# SCP_Controller.net
KiCad netlist of a schematic drawn in Altium Designer
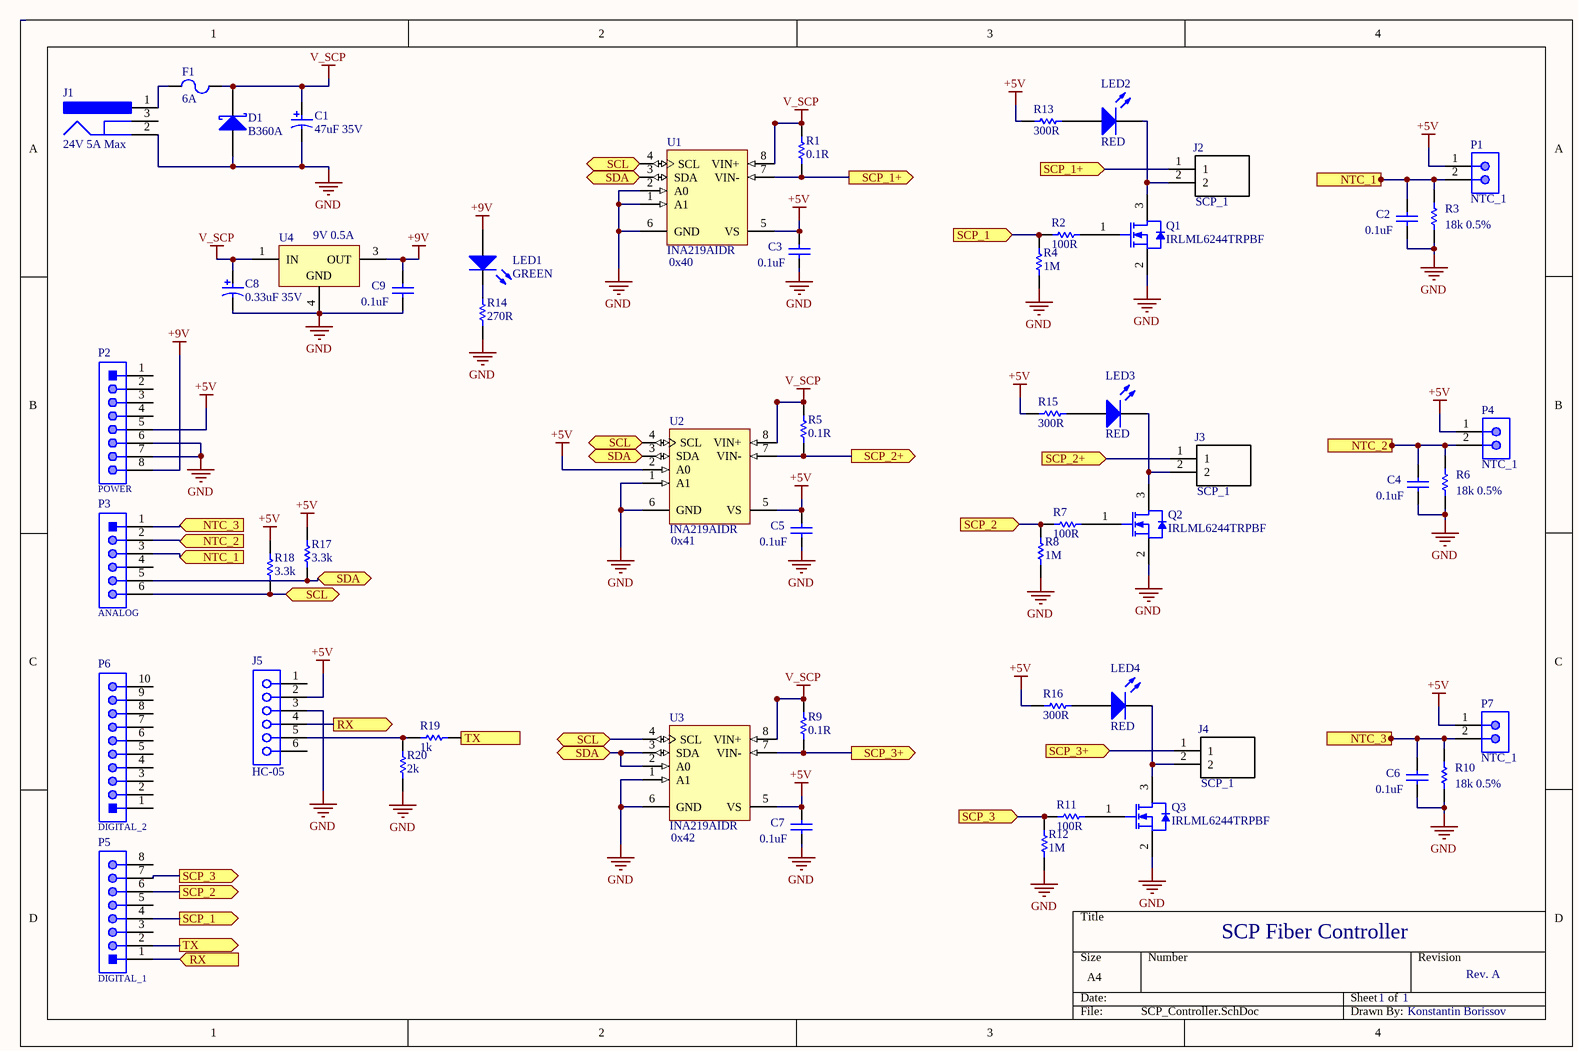
[diagram p0: SCP_Controller.SchDoc]

(export (version "E")
  (design (tool "Eeschema 10.0.6"))
  (components
    (comp (ref "C1")
      (value "47uF 35V")
      (footprint "PNSC-FP-V-D_V")
      (fields
        (field (name "MANUFACTURER") "Panasonic")
        (field (name "MANUFACTURER PART NUMBER") "EEE-1VA470WP")
        (field (name "TOLERANCE") "20%")
      )
      (libsource (lib "Altium Content Vault") (part "CAP-P-2"))
    )
    (comp (ref "C2")
      (value "0.1uF")
      (footprint "CAPC1608X90X35NL10T15")
      (fields
        (field (name "MANUFACTURER") "Murata")
        (field (name "MANUFACTURER PART NUMBER") "GCJ188R71E104KA12D")
        (field (name "TOLERANCE") "10%")
      )
      (libsource (lib "Altium Content Vault") (part "CAP"))
    )
    (comp (ref "C3")
      (value "0.1uF")
      (footprint "CAPC1608X90X35NL10T15")
      (fields
        (field (name "MANUFACTURER") "Murata")
        (field (name "MANUFACTURER PART NUMBER") "GCJ188R71E104KA12D")
        (field (name "TOLERANCE") "10%")
      )
      (libsource (lib "Altium Content Vault") (part "CAP"))
    )
    (comp (ref "C4")
      (value "0.1uF")
      (footprint "CAPC1608X90X35NL10T15")
      (fields
        (field (name "MANUFACTURER") "Murata")
        (field (name "MANUFACTURER PART NUMBER") "GCJ188R71E104KA12D")
        (field (name "TOLERANCE") "10%")
      )
      (libsource (lib "Altium Content Vault") (part "CAP"))
    )
    (comp (ref "C5")
      (value "0.1uF")
      (footprint "CAPC1608X90X35NL10T15")
      (fields
        (field (name "MANUFACTURER") "Murata")
        (field (name "MANUFACTURER PART NUMBER") "GCJ188R71E104KA12D")
        (field (name "TOLERANCE") "10%")
      )
      (libsource (lib "Altium Content Vault") (part "CAP"))
    )
    (comp (ref "C6")
      (value "0.1uF")
      (footprint "CAPC1608X90X35NL10T15")
      (fields
        (field (name "MANUFACTURER") "Murata")
        (field (name "MANUFACTURER PART NUMBER") "GCJ188R71E104KA12D")
        (field (name "TOLERANCE") "10%")
      )
      (libsource (lib "Altium Content Vault") (part "CAP"))
    )
    (comp (ref "C7")
      (value "0.1uF")
      (footprint "CAPC1608X90X35NL10T15")
      (fields
        (field (name "MANUFACTURER") "Murata")
        (field (name "MANUFACTURER PART NUMBER") "GCJ188R71E104KA12D")
        (field (name "TOLERANCE") "10%")
      )
      (libsource (lib "Altium Content Vault") (part "CAP"))
    )
    (comp (ref "C8")
      (value "0.33uF 35V")
      (footprint "KEMT-A-3216-18-2_M")
      (fields
        (field (name "MANUFACTURER") "KEMET")
        (field (name "MANUFACTURER PART NUMBER") "T491A334K035AT")
        (field (name "TOLERANCE") "10%")
      )
      (libsource (lib "Altium Content Vault") (part "CAP-P-2"))
    )
    (comp (ref "C9")
      (value "0.1uF")
      (footprint "CAPC1608X90X35NL10T15")
      (fields
        (field (name "MANUFACTURER") "Murata")
        (field (name "MANUFACTURER PART NUMBER") "GCJ188R71E104KA12D")
        (field (name "TOLERANCE") "10%")
      )
      (libsource (lib "Altium Content Vault") (part "CAP"))
    )
    (comp (ref "D1")
      (value "B360A")
      (footprint "DIOD-B360A_V")
      (description "Schottky Barrier Rectifier, 3 A, -55 to 150 degC, 2-Pin Molded, RoHS, Tape and Reel")
      (fields
        (field (name "MANUFACTURER") "DiodesIncorporated")
        (field (name "MANUFACTURER PART NUMBER") "B360A-13-F")
      )
      (libsource (lib "Altium Content Vault") (part "DSKY-AK-2"))
    )
    (comp (ref "F1")
      (value "6A")
      (footprint "LFUS-0468001.NR_V")
      (fields (field (name "MANUFACTURER") "Bel TRP") (field (name "MANUFACTURER PART NUMBER") "C1F6"))
      (libsource (lib "Altium Content Vault") (part "FUSE-2"))
    )
    (comp (ref "J1")
      (value "24V 5A Max")
      (footprint "CUI-PJ-102A_V")
      (description "DC Power Jack, 5 A, -25 to 85 degC, 3-Pin THD, RoHS")
      (fields (field (name "MANUFACTURER") "CUI") (field (name "MANUFACTURER PART NUMBER") "PJ-102AH"))
      (libsource (lib "Altium Content Vault") (part "JACK-2CD3-RN"))
    )
    (comp (ref "J2")
      (value "SCP_1")
      (footprint "*CUI_TBP02R1-381-02BE")
      (fields
        (field (name "MANUFACTURER") "CUI")
        (field (name "MANUFACTURER PART NUMBER") "TBP02R1-381-02BE")
      )
      (libsource (lib "TBP02R1-381-02BE") (part "TBP02R1-381-02BE"))
    )
    (comp (ref "J3")
      (value "SCP_1")
      (footprint "*CUI_TBP02R1-381-02BE")
      (fields
        (field (name "MANUFACTURER") "CUI")
        (field (name "MANUFACTURER PART NUMBER") "TBP02R1-381-02BE")
      )
      (libsource (lib "TBP02R1-381-02BE") (part "TBP02R1-381-02BE"))
    )
    (comp (ref "J4")
      (value "SCP_1")
      (footprint "*CUI_TBP02R1-381-02BE")
      (fields
        (field (name "MANUFACTURER") "CUI")
        (field (name "MANUFACTURER PART NUMBER") "TBP02R1-381-02BE")
      )
      (libsource (lib "TBP02R1-381-02BE") (part "TBP02R1-381-02BE"))
    )
    (comp (ref "J5")
      (value "HC-05")
      (footprint "SMTC-SSW-106-02-X-S")
      (description "SQ Post Socket, Through-hole, Vertical, -55 to 105 degC, 2.54mm Pitch, 6-Pin, Female, RoHS")
      (fields (field (name "MANUFACTURER") "Samtec") (field (name "PARTNUMBER") "SSW-106-02-T-S"))
      (libsource (lib "Altium Content Vault") (part "SMTC-SSW-106-02-X-S-X"))
    )
    (comp (ref "LED1")
      (value "GREEN")
      (footprint "0603_A")
      (description "SMD mono-color Chip LED, WL-SMCW, Bright Green")
      (fields (field (name "PARTNUMBER") "150060VS75000") (field (name "MANUFACTURER") "Wuerth Elektronik"))
      (libsource (lib "Altium Content Vault") (part "WE-LED_K1A2-2"))
    )
    (comp (ref "LED2")
      (value "RED")
      (footprint "0603_A")
      (description "SMD mono-color Chip LED, WL-SMCW, Red")
      (fields (field (name "MANUFACTURER") "Wuerth Elektronik") (field (name "PARTNUMBER") "150060RS75000"))
      (libsource (lib "Altium Content Vault") (part "WE-LED_K1A2-2"))
    )
    (comp (ref "LED3")
      (value "RED")
      (footprint "0603_A")
      (description "SMD mono-color Chip LED, WL-SMCW, Red")
      (fields (field (name "MANUFACTURER") "Wuerth Elektronik") (field (name "PARTNUMBER") "150060RS75000"))
      (libsource (lib "Altium Content Vault") (part "WE-LED_K1A2-2"))
    )
    (comp (ref "LED4")
      (value "RED")
      (footprint "0603_A")
      (description "SMD mono-color Chip LED, WL-SMCW, Red")
      (fields (field (name "MANUFACTURER") "Wuerth Elektronik") (field (name "PARTNUMBER") "150060RS75000"))
      (libsource (lib "Altium Content Vault") (part "WE-LED_K1A2-2"))
    )
    (comp (ref "P1")
      (value "NTC_1")
      (footprint "JST-B2B-XH-A_V")
      (fields (field (name "MANUFACTURER") "JST"))
      (libsource (lib "Altium Content Vault") (part "CN-1P-M-R2"))
    )
    (comp (ref "P2")
      (value "POWER")
      (footprint "61300811121")
      (description "THT Vertical Pin Header WR-PHD, Pitch 2.54 mm, Single Row, 8 pins")
      (fields
        (field (name "MANUFACTURER") "Wurth Elektronik")
        (field (name "PART NUMBER") "61300811121")
        (field (name "PUBLISHER") "WurthElektronik")
      )
      (libsource (lib "") (part "WE-CN-1P-M-R8_1"))
    )
    (comp (ref "P3")
      (value "ANALOG")
      (footprint "61300611121")
      (description "THT Vertical Pin Header WR-PHD, Pitch 2.54 mm, Single Row, 6 pins")
      (fields
        (field (name "PART NUMBER") "61300611121")
        (field (name "MANUFACTURER") "Wurth Elektronik")
        (field (name "PUBLISHER") "WurthElektronik")
      )
      (libsource (lib "Altium Content Vault") (part "WE-CN-1P-M-R6"))
    )
    (comp (ref "P4")
      (value "NTC_1")
      (footprint "JST-B2B-XH-A_V")
      (fields (field (name "MANUFACTURER") "JST"))
      (libsource (lib "Altium Content Vault") (part "CN-1P-M-R2"))
    )
    (comp (ref "P5")
      (value "DIGITAL_1")
      (footprint "61300811121")
      (description "THT Vertical Pin Header WR-PHD, Pitch 2.54 mm, Single Row, 8 pins")
      (fields
        (field (name "MANUFACTURER") "Wurth Elektronik")
        (field (name "PART NUMBER") "61300811121")
        (field (name "PUBLISHER") "WurthElektronik")
      )
      (libsource (lib "Altium Content Vault") (part "WE-CN-1P-M-R8"))
    )
    (comp (ref "P6")
      (value "DIGITAL_2")
      (footprint "61301011121")
      (description "THT Vertical Pin Header WR-PHD, Pitch 2.54 mm, Single Row, 10 pins")
      (fields
        (field (name "MANUFACTURER") "Wurth Elektronik")
        (field (name "PART NUMBER") "61301011121")
        (field (name "PUBLISHER") "WurthElektronik")
      )
      (libsource (lib "Altium Content Vault") (part "WE-CN-1P-M-R10"))
    )
    (comp (ref "P7")
      (value "NTC_1")
      (footprint "JST-B2B-XH-A_V")
      (fields (field (name "MANUFACTURER") "JST"))
      (libsource (lib "Altium Content Vault") (part "CN-1P-M-R2"))
    )
    (comp (ref "Q1")
      (value "IRLML6244TRPBF")
      (footprint "INTR-SOT23-3_V")
      (description "HEXFET(R) Power MOSFET\r\n, 20 V, -55 to 150 degC, 3-Pin SOT-23, RoHS, Tape and Reel")
      (fields (field (name "MANUFACTURER") "International Rectifier"))
      (libsource (lib "Altium Content Vault") (part "NEMOS-GSD-3"))
    )
    (comp (ref "Q2")
      (value "IRLML6244TRPBF")
      (footprint "INTR-SOT23-3_V")
      (description "HEXFET(R) Power MOSFET\r\n, 20 V, -55 to 150 degC, 3-Pin SOT-23, RoHS, Tape and Reel")
      (fields (field (name "MANUFACTURER") "International Rectifier"))
      (libsource (lib "Altium Content Vault") (part "NEMOS-GSD-3"))
    )
    (comp (ref "Q3")
      (value "IRLML6244TRPBF")
      (footprint "INTR-SOT23-3_V")
      (description "HEXFET(R) Power MOSFET\r\n, 20 V, -55 to 150 degC, 3-Pin SOT-23, RoHS, Tape and Reel")
      (fields (field (name "MANUFACTURER") "International Rectifier"))
      (libsource (lib "Altium Content Vault") (part "NEMOS-GSD-3"))
    )
    (comp (ref "R1")
      (value "0.1R")
      (footprint "RESC6432X89X76LL25T25")
      (description "RES 0.1 OHM 1% 1W 2512")
      (fields
        (field (name "MANUFACTURER") "Yageo")
        (field (name "MANUFACTURER PART NUMBER") "RL2512FK-070R1L")
      )
      (libsource (lib "Altium Content Vault") (part "RES-2"))
    )
    (comp (ref "R2")
      (value "100R")
      (footprint "RESC2013X60X35ML10T20")
      (description "Chip Resistor, 100 Ohm, +/-1%, 0.125 W, -55 to 155 degC, 0805 (2012 Metric), RoHS, Tape and Reel")
      (fields (field (name "TOLERANCE") "1%") (field (name "MANUFACTURER") "Yageo"))
      (libsource (lib "Altium Content Vault") (part "RES-2"))
    )
    (comp (ref "R3")
      (value "18k 0.5%")
      (footprint "RESC2013X70X40NL20T20")
      (fields
        (field (name "MANUFACTURER") "Panasonic")
        (field (name "MANUFACTURER PART NUMBER") "ERA-6AED183V")
        (field (name "TOLERANCE") "0.5%")
      )
      (libsource (lib "Altium Content Vault") (part "RES"))
    )
    (comp (ref "R4")
      (value "1M")
      (footprint "RESC2013X70X40NL20T20")
      (fields
        (field (name "MANUFACTURER") "Yageo")
        (field (name "MANUFACTURER PART NUMBER") "RC0805FR-071ML")
        (field (name "TOLERANCE") "1%")
      )
      (libsource (lib "Altium Content Vault") (part "RES"))
    )
    (comp (ref "R5")
      (value "0.1R")
      (footprint "RESC6432X89X76LL25T25")
      (description "RES 0.1 OHM 1% 1W 2512")
      (fields
        (field (name "MANUFACTURER") "Yageo")
        (field (name "MANUFACTURER PART NUMBER") "RL2512FK-070R1L")
      )
      (libsource (lib "Altium Content Vault") (part "RES-2"))
    )
    (comp (ref "R6")
      (value "18k 0.5%")
      (footprint "RESC2013X70X40NL20T20")
      (fields
        (field (name "MANUFACTURER") "Panasonic")
        (field (name "MANUFACTURER PART NUMBER") "ERA-6AED183V")
        (field (name "TOLERANCE") "0.5%")
      )
      (libsource (lib "Altium Content Vault") (part "RES"))
    )
    (comp (ref "R7")
      (value "100R")
      (footprint "RESC2013X60X35ML10T20")
      (description "Chip Resistor, 100 Ohm, +/-1%, 0.125 W, -55 to 155 degC, 0805 (2012 Metric), RoHS, Tape and Reel")
      (fields (field (name "TOLERANCE") "1%") (field (name "MANUFACTURER") "Yageo"))
      (libsource (lib "Altium Content Vault") (part "RES-2"))
    )
    (comp (ref "R8")
      (value "1M")
      (footprint "RESC2013X70X40NL20T20")
      (fields
        (field (name "MANUFACTURER") "Yageo")
        (field (name "MANUFACTURER PART NUMBER") "RC0805FR-071ML")
        (field (name "TOLERANCE") "1%")
      )
      (libsource (lib "Altium Content Vault") (part "RES"))
    )
    (comp (ref "R9")
      (value "0.1R")
      (footprint "RESC6432X89X76LL25T25")
      (description "RES 0.1 OHM 1% 1W 2512")
      (fields
        (field (name "MANUFACTURER") "Yageo")
        (field (name "MANUFACTURER PART NUMBER") "RL2512FK-070R1L")
      )
      (libsource (lib "Altium Content Vault") (part "RES-2"))
    )
    (comp (ref "R10")
      (value "18k 0.5%")
      (footprint "RESC2013X70X40NL20T20")
      (fields
        (field (name "MANUFACTURER") "Panasonic")
        (field (name "MANUFACTURER PART NUMBER") "ERA-6AED183V")
        (field (name "TOLERANCE") "0.5%")
      )
      (libsource (lib "Altium Content Vault") (part "RES"))
    )
    (comp (ref "R11")
      (value "100R")
      (footprint "RESC2013X60X35ML10T20")
      (description "Chip Resistor, 100 Ohm, +/-1%, 0.125 W, -55 to 155 degC, 0805 (2012 Metric), RoHS, Tape and Reel")
      (fields (field (name "TOLERANCE") "1%") (field (name "MANUFACTURER") "Yageo"))
      (libsource (lib "Altium Content Vault") (part "RES-2"))
    )
    (comp (ref "R12")
      (value "1M")
      (footprint "RESC2013X70X40NL20T20")
      (fields
        (field (name "MANUFACTURER") "Yageo")
        (field (name "MANUFACTURER PART NUMBER") "RC0805FR-071ML")
        (field (name "TOLERANCE") "1%")
      )
      (libsource (lib "Altium Content Vault") (part "RES"))
    )
    (comp (ref "R13")
      (value "300R")
      (footprint "RESC2013X60X35LL10T20")
      (description "Chip Resistor, 300 Ohm, +/- 1%, 125 mW, -55 to 155 degC, 0805 (2012 Metric), RoHS, Tape and Reel")
      (fields (field (name "MANUFACTURER") "Yageo") (field (name "TOLERANCE") "1%"))
      (libsource (lib "Altium Content Vault") (part "RES-2"))
    )
    (comp (ref "R14")
      (value "270R")
      (footprint "RESC2013X60X35LL10T20")
      (description "Chip Resistor, 270 Ohm, +/- 1%, 125 mW, -55 to 155 degC, 0805 (2012 Metric), RoHS, Tape and Reel")
      (fields
        (field (name "MANUFACTURER") "Yageo")
        (field (name "MANUFACTURER PART NUMBER") "RC0805FR-07270RL")
      )
      (libsource (lib "Altium Content Vault") (part "RES-2"))
    )
    (comp (ref "R15")
      (value "300R")
      (footprint "RESC2013X60X35LL10T20")
      (description "Chip Resistor, 300 Ohm, +/- 1%, 125 mW, -55 to 155 degC, 0805 (2012 Metric), RoHS, Tape and Reel")
      (fields (field (name "MANUFACTURER") "Yageo") (field (name "TOLERANCE") "1%"))
      (libsource (lib "Altium Content Vault") (part "RES-2"))
    )
    (comp (ref "R16")
      (value "300R")
      (footprint "RESC2013X60X35LL10T20")
      (description "Chip Resistor, 300 Ohm, +/- 1%, 125 mW, -55 to 155 degC, 0805 (2012 Metric), RoHS, Tape and Reel")
      (fields (field (name "MANUFACTURER") "Yageo") (field (name "TOLERANCE") "1%"))
      (libsource (lib "Altium Content Vault") (part "RES-2"))
    )
    (comp (ref "R17")
      (value "3.3k")
      (footprint "RESC2013X60X35ML10T20")
      (description "Chip Resistor, 3.3 KOhm, +/- 1%, 0.125 W, -55 to 155 degC, 0805 (2012 Metric), RoHS, Tape and Reel")
      (fields (field (name "TOLERANCE") "1%") (field (name "MANUFACTURER") "Yageo"))
      (libsource (lib "Altium Content Vault") (part "RES-2"))
    )
    (comp (ref "R18")
      (value "3.3k")
      (footprint "RESC2013X60X35ML10T20")
      (description "Chip Resistor, 3.3 KOhm, +/- 1%, 0.125 W, -55 to 155 degC, 0805 (2012 Metric), RoHS, Tape and Reel")
      (fields (field (name "TOLERANCE") "1%") (field (name "MANUFACTURER") "Yageo"))
      (libsource (lib "Altium Content Vault") (part "RES-2"))
    )
    (comp (ref "R19")
      (value "1k")
      (footprint "RESC2013X60X35ML10T20")
      (description "Chip Resistor, 1 KOhm, +/- 1%, 125 mW, -55 to 155 degC, 0805 (2012 Metric), RoHS, Tape and Reel")
      (fields (field (name "TOLERANCE") "1%") (field (name "MANUFACTURER") "Yageo"))
      (libsource (lib "Altium Content Vault") (part "RES-2"))
    )
    (comp (ref "R20")
      (value "2k")
      (footprint "RESC2013X60X35ML10T20")
      (description "Chip Resistor, 2 KOhm, +/- 1%, 125 mW, -55 to 155 degC, 0805 (2012 Metric), RoHS, Tape and Reel")
      (fields
        (field (name "MANUFACTURER") "Yageo")
        (field (name "MANUFACTURER PART NUMBER") "RC0805FR-072KL")
      )
      (libsource (lib "Altium Content Vault") (part "RES-2"))
    )
    (comp (ref "U1")
      (value "INA219AIDR")
      (footprint "D0008A_L")
      (description "IC CURRENT MONITOR 1% 8SOIC")
      (fields (field (name "MANUFACTURER") "Texas Instruments") (field (name "ADDRESS") "0x40"))
      (libsource (lib "Altium Content Vault") (part "TI-INA219D8"))
    )
    (comp (ref "U2")
      (value "INA219AIDR")
      (footprint "D0008A_L")
      (description "IC CURRENT MONITOR 1% 8SOIC")
      (fields (field (name "MANUFACTURER") "Texas Instruments") (field (name "ADDRESS") "0x41"))
      (libsource (lib "Altium Content Vault") (part "TI-INA219D8"))
    )
    (comp (ref "U3")
      (value "INA219AIDR")
      (footprint "D0008A_L")
      (description "IC CURRENT MONITOR 1% 8SOIC")
      (fields (field (name "MANUFACTURER") "Texas Instruments") (field (name "ADDRESS") "0x42"))
      (libsource (lib "Altium Content Vault") (part "TI-INA219D8"))
    )
    (comp (ref "U4")
      (value "9V 0.5A")
      (footprint "TO-252_N")
      (fields
        (field (name "MANUFACTURER") "ON Semiconductor")
        (field (name "MANUFACTURER PART NUMBER") "MC78M09CDTRKG")
      )
      (libsource (lib "Altium Content Vault") (part "PM-REG-L4940-SOT3"))
    )
  )
  (nets
    (net (code "1") (name "+5V") (class "Default")
      (node (ref "C3") (pin "1") (pinfunction "1_1") (pintype "passive"))
      (node (ref "C5") (pin "1") (pinfunction "1_1") (pintype "passive"))
      (node (ref "C7") (pin "1") (pinfunction "1_1") (pintype "passive"))
      (node (ref "J5") (pin "2") (pinfunction "2_2") (pintype "passive"))
      (node (ref "P1") (pin "1") (pinfunction "1_1") (pintype "passive"))
      (node (ref "P2") (pin "5") (pinfunction "5_5") (pintype "passive"))
      (node (ref "P4") (pin "1") (pinfunction "1_1") (pintype "passive"))
      (node (ref "P7") (pin "1") (pinfunction "1_1") (pintype "passive"))
      (node (ref "R13") (pin "1") (pinfunction "1_1") (pintype "passive"))
      (node (ref "R15") (pin "1") (pinfunction "1_1") (pintype "passive"))
      (node (ref "R16") (pin "1") (pinfunction "1_1") (pintype "passive"))
      (node (ref "R17") (pin "2") (pinfunction "2_2") (pintype "passive"))
      (node (ref "R18") (pin "2") (pinfunction "2_2") (pintype "passive"))
      (node (ref "U1") (pin "5") (pinfunction "VS_5") (pintype "power_in"))
      (node (ref "U2") (pin "2") (pinfunction "A0_2") (pintype "input"))
      (node (ref "U2") (pin "5") (pinfunction "VS_5") (pintype "power_in"))
      (node (ref "U3") (pin "5") (pinfunction "VS_5") (pintype "power_in"))
    )
    (net (code "2") (name "+9V") (class "Default")
      (node (ref "C9") (pin "1") (pinfunction "1_1") (pintype "passive"))
      (node (ref "LED1") (pin "2") (pinfunction "A_2") (pintype "passive"))
      (node (ref "P2") (pin "8") (pinfunction "8_8") (pintype "passive"))
      (node (ref "U4") (pin "3") (pinfunction "OUT_3") (pintype "power_in"))
    )
    (net (code "3") (name "/NTC_1") (class "Default")
      (node (ref "C2") (pin "1") (pinfunction "1_1") (pintype "passive"))
      (node (ref "P1") (pin "2") (pinfunction "2_2") (pintype "passive"))
      (node (ref "P3") (pin "3") (pinfunction "3_3") (pintype "passive"))
      (node (ref "R3") (pin "2") (pinfunction "2_2") (pintype "passive"))
    )
    (net (code "4") (name "/NTC_2") (class "Default")
      (node (ref "C4") (pin "1") (pinfunction "1_1") (pintype "passive"))
      (node (ref "P3") (pin "2") (pinfunction "2_2") (pintype "passive"))
      (node (ref "P4") (pin "2") (pinfunction "2_2") (pintype "passive"))
      (node (ref "R6") (pin "2") (pinfunction "2_2") (pintype "passive"))
    )
    (net (code "5") (name "/NTC_3") (class "Default")
      (node (ref "C6") (pin "1") (pinfunction "1_1") (pintype "passive"))
      (node (ref "P3") (pin "1") (pinfunction "1_1") (pintype "passive"))
      (node (ref "P7") (pin "2") (pinfunction "2_2") (pintype "passive"))
      (node (ref "R10") (pin "2") (pinfunction "2_2") (pintype "passive"))
    )
    (net (code "6") (name "/RX") (class "Default")
      (node (ref "J5") (pin "4") (pinfunction "4_4") (pintype "passive"))
      (node (ref "P5") (pin "1") (pinfunction "1_1") (pintype "passive"))
    )
    (net (code "7") (name "/SCL") (class "Default")
      (node (ref "P3") (pin "6") (pinfunction "6_6") (pintype "passive"))
      (node (ref "R18") (pin "1") (pinfunction "1_1") (pintype "passive"))
      (node (ref "U1") (pin "4") (pinfunction "SCL_4") (pintype "bidirectional"))
      (node (ref "U2") (pin "4") (pinfunction "SCL_4") (pintype "bidirectional"))
      (node (ref "U3") (pin "4") (pinfunction "SCL_4") (pintype "bidirectional"))
    )
    (net (code "8") (name "/SCP_1") (class "Default")
      (node (ref "P5") (pin "4") (pinfunction "4_4") (pintype "passive"))
      (node (ref "R2") (pin "1") (pinfunction "1_1") (pintype "passive"))
      (node (ref "R4") (pin "2") (pinfunction "2_2") (pintype "passive"))
    )
    (net (code "9") (name "/SCP_1+") (class "Default")
      (node (ref "J2") (pin "1") (pinfunction "1_1") (pintype "passive"))
      (node (ref "R1") (pin "1") (pinfunction "1_1") (pintype "passive"))
      (node (ref "U1") (pin "7") (pinfunction "VIN-_7") (pintype "input"))
    )
    (net (code "10") (name "/SCP_2") (class "Default")
      (node (ref "P5") (pin "6") (pinfunction "6_6") (pintype "passive"))
      (node (ref "R7") (pin "1") (pinfunction "1_1") (pintype "passive"))
      (node (ref "R8") (pin "2") (pinfunction "2_2") (pintype "passive"))
    )
    (net (code "11") (name "/SCP_2+") (class "Default")
      (node (ref "J3") (pin "1") (pinfunction "1_1") (pintype "passive"))
      (node (ref "R5") (pin "1") (pinfunction "1_1") (pintype "passive"))
      (node (ref "U2") (pin "7") (pinfunction "VIN-_7") (pintype "input"))
    )
    (net (code "12") (name "/SCP_3") (class "Default")
      (node (ref "P5") (pin "7") (pinfunction "7_7") (pintype "passive"))
      (node (ref "R11") (pin "1") (pinfunction "1_1") (pintype "passive"))
      (node (ref "R12") (pin "2") (pinfunction "2_2") (pintype "passive"))
    )
    (net (code "13") (name "/SCP_3+") (class "Default")
      (node (ref "J4") (pin "1") (pinfunction "1_1") (pintype "passive"))
      (node (ref "R9") (pin "1") (pinfunction "1_1") (pintype "passive"))
      (node (ref "U3") (pin "7") (pinfunction "VIN-_7") (pintype "input"))
    )
    (net (code "14") (name "/SDA") (class "Default")
      (node (ref "P3") (pin "5") (pinfunction "5_5") (pintype "passive"))
      (node (ref "R17") (pin "1") (pinfunction "1_1") (pintype "passive"))
      (node (ref "U1") (pin "3") (pinfunction "SDA_3") (pintype "bidirectional"))
      (node (ref "U2") (pin "3") (pinfunction "SDA_3") (pintype "bidirectional"))
      (node (ref "U3") (pin "2") (pinfunction "A0_2") (pintype "input"))
      (node (ref "U3") (pin "3") (pinfunction "SDA_3") (pintype "bidirectional"))
    )
    (net (code "15") (name "/TX") (class "Default")
      (node (ref "P5") (pin "2") (pinfunction "2_2") (pintype "passive"))
      (node (ref "R19") (pin "1") (pinfunction "1_1") (pintype "passive"))
    )
    (net (code "16") (name "GND") (class "Default")
      (node (ref "C1") (pin "2") (pinfunction "2_2") (pintype "passive"))
      (node (ref "C2") (pin "2") (pinfunction "2_2") (pintype "passive"))
      (node (ref "C3") (pin "2") (pinfunction "2_2") (pintype "passive"))
      (node (ref "C4") (pin "2") (pinfunction "2_2") (pintype "passive"))
      (node (ref "C5") (pin "2") (pinfunction "2_2") (pintype "passive"))
      (node (ref "C6") (pin "2") (pinfunction "2_2") (pintype "passive"))
      (node (ref "C7") (pin "2") (pinfunction "2_2") (pintype "passive"))
      (node (ref "C8") (pin "2") (pinfunction "2_2") (pintype "passive"))
      (node (ref "C9") (pin "2") (pinfunction "2_2") (pintype "passive"))
      (node (ref "D1") (pin "1") (pinfunction "A_1") (pintype "passive"))
      (node (ref "J1") (pin "2") (pinfunction "3_2") (pintype "passive"))
      (node (ref "J5") (pin "3") (pinfunction "3_3") (pintype "passive"))
      (node (ref "P2") (pin "6") (pinfunction "6_6") (pintype "passive"))
      (node (ref "P2") (pin "7") (pinfunction "7_7") (pintype "passive"))
      (node (ref "Q1") (pin "2") (pinfunction "S_2") (pintype "passive"))
      (node (ref "Q2") (pin "2") (pinfunction "S_2") (pintype "passive"))
      (node (ref "Q3") (pin "2") (pinfunction "S_2") (pintype "passive"))
      (node (ref "R10") (pin "1") (pinfunction "1_1") (pintype "passive"))
      (node (ref "R12") (pin "1") (pinfunction "1_1") (pintype "passive"))
      (node (ref "R14") (pin "1") (pinfunction "1_1") (pintype "passive"))
      (node (ref "R20") (pin "1") (pinfunction "1_1") (pintype "passive"))
      (node (ref "R3") (pin "1") (pinfunction "1_1") (pintype "passive"))
      (node (ref "R4") (pin "1") (pinfunction "1_1") (pintype "passive"))
      (node (ref "R6") (pin "1") (pinfunction "1_1") (pintype "passive"))
      (node (ref "R8") (pin "1") (pinfunction "1_1") (pintype "passive"))
      (node (ref "U1") (pin "1") (pinfunction "A1_1") (pintype "input"))
      (node (ref "U1") (pin "2") (pinfunction "A0_2") (pintype "input"))
      (node (ref "U1") (pin "6") (pinfunction "GND_6") (pintype "power_in"))
      (node (ref "U2") (pin "1") (pinfunction "A1_1") (pintype "input"))
      (node (ref "U2") (pin "6") (pinfunction "GND_6") (pintype "power_in"))
      (node (ref "U3") (pin "1") (pinfunction "A1_1") (pintype "input"))
      (node (ref "U3") (pin "6") (pinfunction "GND_6") (pintype "power_in"))
      (node (ref "U4") (pin "4") (pinfunction "GND_4") (pintype "power_in"))
    )
    (net (code "17") (name "Net-(F1-Pad1)") (class "Default")
      (node (ref "F1") (pin "1") (pinfunction "1_1") (pintype "passive"))
      (node (ref "J1") (pin "1") (pinfunction "1_1") (pintype "passive"))
    )
    (net (code "18") (name "Net-(J5-Pad5)") (class "Default")
      (node (ref "J5") (pin "5") (pinfunction "5_5") (pintype "passive"))
      (node (ref "R19") (pin "2") (pinfunction "2_2") (pintype "passive"))
      (node (ref "R20") (pin "2") (pinfunction "2_2") (pintype "passive"))
    )
    (net (code "19") (name "Net-(LED1-K)") (class "Default")
      (node (ref "LED1") (pin "1") (pinfunction "K_1") (pintype "passive"))
      (node (ref "R14") (pin "2") (pinfunction "2_2") (pintype "passive"))
    )
    (net (code "20") (name "Net-(LED2-A)") (class "Default")
      (node (ref "LED2") (pin "2") (pinfunction "A_2") (pintype "passive"))
      (node (ref "R13") (pin "2") (pinfunction "2_2") (pintype "passive"))
    )
    (net (code "21") (name "Net-(LED2-K)") (class "Default")
      (node (ref "J2") (pin "2") (pinfunction "2_2") (pintype "passive"))
      (node (ref "LED2") (pin "1") (pinfunction "K_1") (pintype "passive"))
      (node (ref "Q1") (pin "3") (pinfunction "D_3") (pintype "passive"))
    )
    (net (code "22") (name "Net-(LED3-A)") (class "Default")
      (node (ref "LED3") (pin "2") (pinfunction "A_2") (pintype "passive"))
      (node (ref "R15") (pin "2") (pinfunction "2_2") (pintype "passive"))
    )
    (net (code "23") (name "Net-(LED3-K)") (class "Default")
      (node (ref "J3") (pin "2") (pinfunction "2_2") (pintype "passive"))
      (node (ref "LED3") (pin "1") (pinfunction "K_1") (pintype "passive"))
      (node (ref "Q2") (pin "3") (pinfunction "D_3") (pintype "passive"))
    )
    (net (code "24") (name "Net-(LED4-A)") (class "Default")
      (node (ref "LED4") (pin "2") (pinfunction "A_2") (pintype "passive"))
      (node (ref "R16") (pin "2") (pinfunction "2_2") (pintype "passive"))
    )
    (net (code "25") (name "Net-(LED4-K)") (class "Default")
      (node (ref "J4") (pin "2") (pinfunction "2_2") (pintype "passive"))
      (node (ref "LED4") (pin "1") (pinfunction "K_1") (pintype "passive"))
      (node (ref "Q3") (pin "3") (pinfunction "D_3") (pintype "passive"))
    )
    (net (code "26") (name "Net-(Q1-G)") (class "Default")
      (node (ref "Q1") (pin "1") (pinfunction "G_1") (pintype "passive"))
      (node (ref "R2") (pin "2") (pinfunction "2_2") (pintype "passive"))
    )
    (net (code "27") (name "Net-(Q2-G)") (class "Default")
      (node (ref "Q2") (pin "1") (pinfunction "G_1") (pintype "passive"))
      (node (ref "R7") (pin "2") (pinfunction "2_2") (pintype "passive"))
    )
    (net (code "28") (name "Net-(Q3-G)") (class "Default")
      (node (ref "Q3") (pin "1") (pinfunction "G_1") (pintype "passive"))
      (node (ref "R11") (pin "2") (pinfunction "2_2") (pintype "passive"))
    )
    (net (code "29") (name "V_SCP") (class "Default")
      (node (ref "C1") (pin "1") (pinfunction "1_1") (pintype "passive"))
      (node (ref "C8") (pin "1") (pinfunction "1_1") (pintype "passive"))
      (node (ref "D1") (pin "2") (pinfunction "K_2") (pintype "passive"))
      (node (ref "F1") (pin "2") (pinfunction "2_2") (pintype "passive"))
      (node (ref "R1") (pin "2") (pinfunction "2_2") (pintype "passive"))
      (node (ref "R5") (pin "2") (pinfunction "2_2") (pintype "passive"))
      (node (ref "R9") (pin "2") (pinfunction "2_2") (pintype "passive"))
      (node (ref "U1") (pin "8") (pinfunction "VIN+_8") (pintype "input"))
      (node (ref "U2") (pin "8") (pinfunction "VIN+_8") (pintype "input"))
      (node (ref "U3") (pin "8") (pinfunction "VIN+_8") (pintype "input"))
      (node (ref "U4") (pin "1") (pinfunction "IN_1") (pintype "power_in"))
    )
    (net (code "30") (name "unconnected-(J1-2-Pad3)") (class "Default")
      (node (ref "J1") (pin "3") (pinfunction "2_3") (pintype "passive"))
    )
    (net (code "31") (name "unconnected-(J5-Pad1)") (class "Default")
      (node (ref "J5") (pin "1") (pinfunction "1_1") (pintype "passive"))
    )
    (net (code "32") (name "unconnected-(J5-Pad6)") (class "Default")
      (node (ref "J5") (pin "6") (pinfunction "6_6") (pintype "passive"))
    )
    (net (code "33") (name "unconnected-(P2-Pad1)") (class "Default")
      (node (ref "P2") (pin "1") (pinfunction "1_1") (pintype "passive"))
    )
    (net (code "34") (name "unconnected-(P2-Pad2)") (class "Default")
      (node (ref "P2") (pin "2") (pinfunction "2_2") (pintype "passive"))
    )
    (net (code "35") (name "unconnected-(P2-Pad3)") (class "Default")
      (node (ref "P2") (pin "3") (pinfunction "3_3") (pintype "passive"))
    )
    (net (code "36") (name "unconnected-(P2-Pad4)") (class "Default")
      (node (ref "P2") (pin "4") (pinfunction "4_4") (pintype "passive"))
    )
    (net (code "37") (name "unconnected-(P3-Pad4)") (class "Default")
      (node (ref "P3") (pin "4") (pinfunction "4_4") (pintype "passive"))
    )
    (net (code "38") (name "unconnected-(P5-Pad3)") (class "Default")
      (node (ref "P5") (pin "3") (pinfunction "3_3") (pintype "passive"))
    )
    (net (code "39") (name "unconnected-(P5-Pad5)") (class "Default")
      (node (ref "P5") (pin "5") (pinfunction "5_5") (pintype "passive"))
    )
    (net (code "40") (name "unconnected-(P5-Pad8)") (class "Default")
      (node (ref "P5") (pin "8") (pinfunction "8_8") (pintype "passive"))
    )
    (net (code "41") (name "unconnected-(P6-Pad1)") (class "Default")
      (node (ref "P6") (pin "1") (pinfunction "1_1") (pintype "passive"))
    )
    (net (code "42") (name "unconnected-(P6-Pad2)") (class "Default")
      (node (ref "P6") (pin "2") (pinfunction "2_2") (pintype "passive"))
    )
    (net (code "43") (name "unconnected-(P6-Pad3)") (class "Default")
      (node (ref "P6") (pin "3") (pinfunction "3_3") (pintype "passive"))
    )
    (net (code "44") (name "unconnected-(P6-Pad4)") (class "Default")
      (node (ref "P6") (pin "4") (pinfunction "4_4") (pintype "passive"))
    )
    (net (code "45") (name "unconnected-(P6-Pad5)") (class "Default")
      (node (ref "P6") (pin "5") (pinfunction "5_5") (pintype "passive"))
    )
    (net (code "46") (name "unconnected-(P6-Pad6)") (class "Default")
      (node (ref "P6") (pin "6") (pinfunction "6_6") (pintype "passive"))
    )
    (net (code "47") (name "unconnected-(P6-Pad7)") (class "Default")
      (node (ref "P6") (pin "7") (pinfunction "7_7") (pintype "passive"))
    )
    (net (code "48") (name "unconnected-(P6-Pad8)") (class "Default")
      (node (ref "P6") (pin "8") (pinfunction "8_8") (pintype "passive"))
    )
    (net (code "49") (name "unconnected-(P6-Pad9)") (class "Default")
      (node (ref "P6") (pin "9") (pinfunction "9_9") (pintype "passive"))
    )
    (net (code "50") (name "unconnected-(P6-Pad10)") (class "Default")
      (node (ref "P6") (pin "10") (pinfunction "10_10") (pintype "passive"))
    )
  )
)
